# x-OSC_Gloves.net
KiCad netlist of a schematic drawn in EAGLE
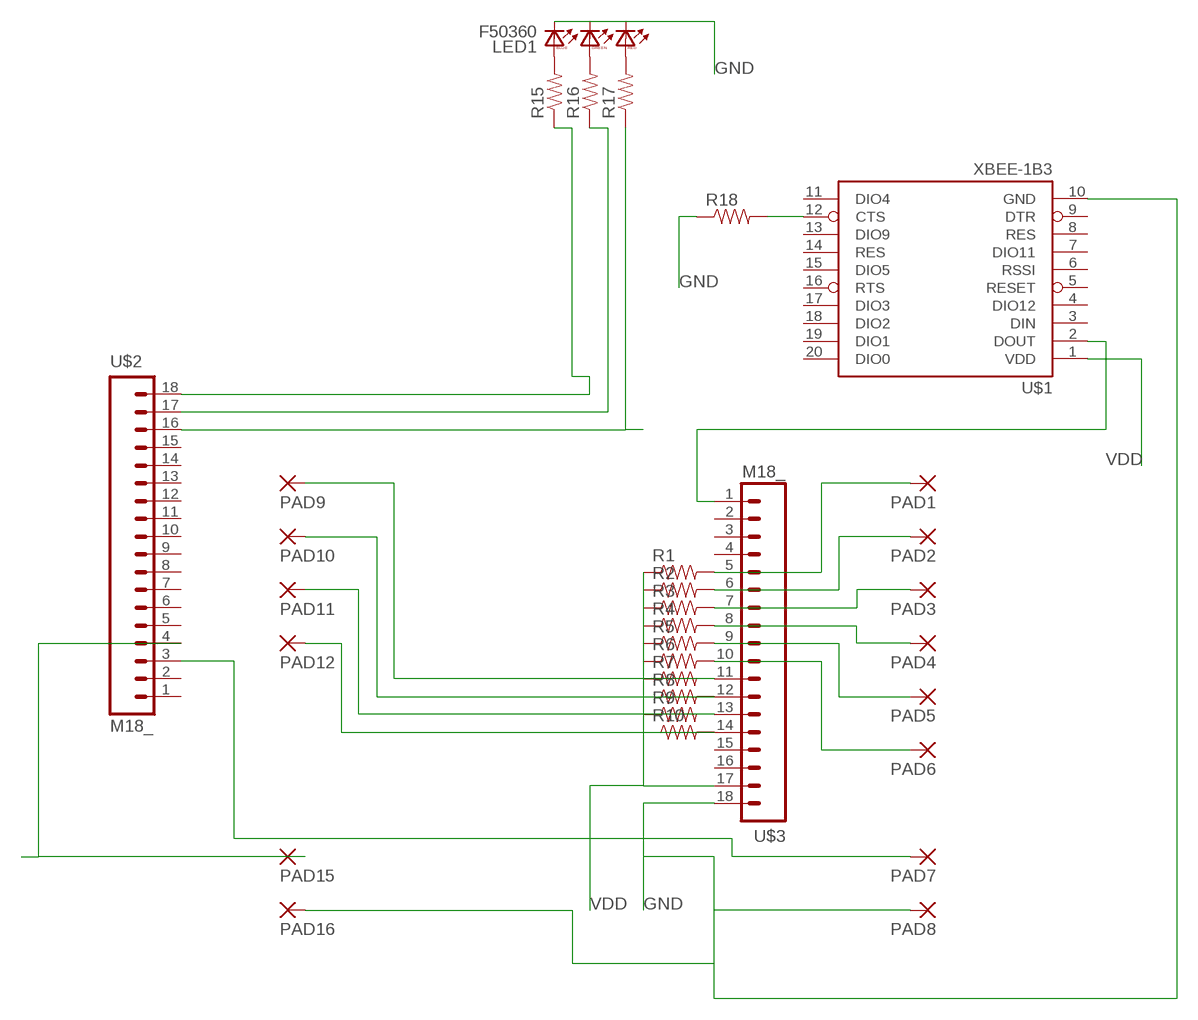
[diagram p0: schematic, sheet 1]

(export (version "E")
  (design (tool "Eeschema 10.0.6"))
  (components
    (comp (ref "LED1")
      (value "F50360")
      (footprint "eagle-import:F50360")
      (libsource (lib "eagle-import") (part "F50360"))
    )
    (comp (ref "PAD1")
      (value "3,81/1,4")
      (footprint "eagle-import:3,81_1,4")
      (libsource (lib "eagle-import") (part "3,81/1,4"))
    )
    (comp (ref "PAD2")
      (value "3,81/1,4")
      (footprint "eagle-import:3,81_1,4")
      (libsource (lib "eagle-import") (part "3,81/1,4"))
    )
    (comp (ref "PAD3")
      (value "3,81/1,4")
      (footprint "eagle-import:3,81_1,4")
      (libsource (lib "eagle-import") (part "3,81/1,4"))
    )
    (comp (ref "PAD4")
      (value "3,81/1,4")
      (footprint "eagle-import:3,81_1,4")
      (libsource (lib "eagle-import") (part "3,81/1,4"))
    )
    (comp (ref "PAD5")
      (value "3,81/1,4")
      (footprint "eagle-import:3,81_1,4")
      (libsource (lib "eagle-import") (part "3,81/1,4"))
    )
    (comp (ref "PAD6")
      (value "3,81/1,4")
      (footprint "eagle-import:3,81_1,4")
      (libsource (lib "eagle-import") (part "3,81/1,4"))
    )
    (comp (ref "PAD7")
      (value "3,81/1,4")
      (footprint "eagle-import:3,81_1,4")
      (libsource (lib "eagle-import") (part "3,81/1,4"))
    )
    (comp (ref "PAD8")
      (value "3,81/1,4")
      (footprint "eagle-import:3,81_1,4")
      (libsource (lib "eagle-import") (part "3,81/1,4"))
    )
    (comp (ref "PAD9")
      (value "3,81/1,4")
      (footprint "eagle-import:3,81_1,4")
      (libsource (lib "eagle-import") (part "3,81/1,4"))
    )
    (comp (ref "PAD10")
      (value "3,81/1,4")
      (footprint "eagle-import:3,81_1,4")
      (libsource (lib "eagle-import") (part "3,81/1,4"))
    )
    (comp (ref "PAD11")
      (value "3,81/1,4")
      (footprint "eagle-import:3,81_1,4")
      (libsource (lib "eagle-import") (part "3,81/1,4"))
    )
    (comp (ref "PAD12")
      (value "3,81/1,4")
      (footprint "eagle-import:3,81_1,4")
      (libsource (lib "eagle-import") (part "3,81/1,4"))
    )
    (comp (ref "PAD15")
      (value "3,81/1,4")
      (footprint "eagle-import:3,81_1,4")
      (libsource (lib "eagle-import") (part "3,81/1,4"))
    )
    (comp (ref "PAD16")
      (value "3,81/1,4")
      (footprint "eagle-import:3,81_1,4")
      (libsource (lib "eagle-import") (part "3,81/1,4"))
    )
    (comp (ref "R1")
      (value "RESISTOR0805-RES")
      (footprint "eagle-import:0805")
      (libsource (lib "eagle-import") (part "RESISTOR0805-RES"))
    )
    (comp (ref "R2")
      (value "RESISTOR0805-RES")
      (footprint "eagle-import:0805")
      (libsource (lib "eagle-import") (part "RESISTOR0805-RES"))
    )
    (comp (ref "R3")
      (value "RESISTOR0805-RES")
      (footprint "eagle-import:0805")
      (libsource (lib "eagle-import") (part "RESISTOR0805-RES"))
    )
    (comp (ref "R4")
      (value "RESISTOR0805-RES")
      (footprint "eagle-import:0805")
      (libsource (lib "eagle-import") (part "RESISTOR0805-RES"))
    )
    (comp (ref "R5")
      (value "RESISTOR0805-RES")
      (footprint "eagle-import:0805")
      (libsource (lib "eagle-import") (part "RESISTOR0805-RES"))
    )
    (comp (ref "R6")
      (value "RESISTOR0805-RES")
      (footprint "eagle-import:0805")
      (libsource (lib "eagle-import") (part "RESISTOR0805-RES"))
    )
    (comp (ref "R7")
      (value "RESISTOR0805-RES")
      (footprint "eagle-import:0805")
      (libsource (lib "eagle-import") (part "RESISTOR0805-RES"))
    )
    (comp (ref "R8")
      (value "RESISTOR0805-RES")
      (footprint "eagle-import:0805")
      (libsource (lib "eagle-import") (part "RESISTOR0805-RES"))
    )
    (comp (ref "R9")
      (value "RESISTOR0805-RES")
      (footprint "eagle-import:0805")
      (libsource (lib "eagle-import") (part "RESISTOR0805-RES"))
    )
    (comp (ref "R10")
      (value "RESISTOR0805-RES")
      (footprint "eagle-import:0805")
      (libsource (lib "eagle-import") (part "RESISTOR0805-RES"))
    )
    (comp (ref "R15")
      (value "RESISTOR0805-RES")
      (footprint "eagle-import:0805")
      (libsource (lib "eagle-import") (part "RESISTOR0805-RES"))
    )
    (comp (ref "R16")
      (value "RESISTOR0805-RES")
      (footprint "eagle-import:0805")
      (libsource (lib "eagle-import") (part "RESISTOR0805-RES"))
    )
    (comp (ref "R17")
      (value "RESISTOR0805-RES")
      (footprint "eagle-import:0805")
      (libsource (lib "eagle-import") (part "RESISTOR0805-RES"))
    )
    (comp (ref "R18")
      (value "RESISTOR0805-RES")
      (footprint "eagle-import:0805")
      (libsource (lib "eagle-import") (part "RESISTOR0805-RES"))
    )
    (comp (ref "U$1")
      (value "XBEE-1B3")
      (footprint "eagle-import:XBEE-SMD")
      (libsource (lib "eagle-import") (part "XBEE-1B3"))
    )
    (comp (ref "U$2")
      (value "M18_")
      (footprint "eagle-import:1X18")
      (libsource (lib "eagle-import") (part "M18_"))
    )
    (comp (ref "U$3")
      (value "M18_")
      (footprint "eagle-import:1X18")
      (libsource (lib "eagle-import") (part "M18_"))
    )
  )
  (nets
    (net (code "1") (name "/GND") (class "Default")
      (node (ref "LED1") (pin "BC") (pinfunction "BC_BC") (pintype "passive"))
      (node (ref "LED1") (pin "GC") (pinfunction "GC_GC") (pintype "passive"))
      (node (ref "LED1") (pin "RC") (pinfunction "RC_RC") (pintype "passive"))
      (node (ref "PAD16") (pin "1") (pinfunction "P_1") (pintype "passive"))
      (node (ref "PAD8") (pin "1") (pinfunction "P_1") (pintype "passive"))
      (node (ref "R18") (pin "1") (pinfunction "1_1") (pintype "passive"))
      (node (ref "U$1") (pin "10") (pinfunction "GND_10") (pintype "power_in"))
      (node (ref "U$3") (pin "18") (pinfunction "18_18") (pintype "passive"))
    )
    (net (code "2") (name "/VDD") (class "Default")
      (node (ref "R1") (pin "1") (pinfunction "1_1") (pintype "passive"))
      (node (ref "R10") (pin "1") (pinfunction "1_1") (pintype "passive"))
      (node (ref "R2") (pin "1") (pinfunction "1_1") (pintype "passive"))
      (node (ref "R3") (pin "1") (pinfunction "1_1") (pintype "passive"))
      (node (ref "R4") (pin "1") (pinfunction "1_1") (pintype "passive"))
      (node (ref "R5") (pin "1") (pinfunction "1_1") (pintype "passive"))
      (node (ref "R6") (pin "1") (pinfunction "1_1") (pintype "passive"))
      (node (ref "R7") (pin "1") (pinfunction "1_1") (pintype "passive"))
      (node (ref "R8") (pin "1") (pinfunction "1_1") (pintype "passive"))
      (node (ref "R9") (pin "1") (pinfunction "1_1") (pintype "passive"))
      (node (ref "U$1") (pin "1") (pinfunction "VDD_1") (pintype "power_in"))
      (node (ref "U$3") (pin "17") (pinfunction "17_17") (pintype "passive"))
    )
    (net (code "3") (name "Net-(LED1-PadBA)") (class "Default")
      (node (ref "LED1") (pin "BA") (pinfunction "BA_BA") (pintype "passive"))
      (node (ref "R15") (pin "2") (pinfunction "2_2") (pintype "passive"))
    )
    (net (code "4") (name "Net-(LED1-PadGA)") (class "Default")
      (node (ref "LED1") (pin "GA") (pinfunction "GA_GA") (pintype "passive"))
      (node (ref "R16") (pin "2") (pinfunction "2_2") (pintype "passive"))
    )
    (net (code "5") (name "Net-(LED1-PadRA)") (class "Default")
      (node (ref "LED1") (pin "RA") (pinfunction "RA_RA") (pintype "passive"))
      (node (ref "R17") (pin "2") (pinfunction "2_2") (pintype "passive"))
    )
    (net (code "6") (name "Net-(PAD1-P)") (class "Default")
      (node (ref "PAD1") (pin "1") (pinfunction "P_1") (pintype "passive"))
      (node (ref "R1") (pin "2") (pinfunction "2_2") (pintype "passive"))
      (node (ref "U$3") (pin "5") (pinfunction "5_5") (pintype "passive"))
    )
    (net (code "7") (name "Net-(PAD2-P)") (class "Default")
      (node (ref "PAD2") (pin "1") (pinfunction "P_1") (pintype "passive"))
      (node (ref "R2") (pin "2") (pinfunction "2_2") (pintype "passive"))
      (node (ref "U$3") (pin "6") (pinfunction "6_6") (pintype "passive"))
    )
    (net (code "8") (name "Net-(PAD3-P)") (class "Default")
      (node (ref "PAD3") (pin "1") (pinfunction "P_1") (pintype "passive"))
      (node (ref "R3") (pin "2") (pinfunction "2_2") (pintype "passive"))
      (node (ref "U$3") (pin "7") (pinfunction "7_7") (pintype "passive"))
    )
    (net (code "9") (name "Net-(PAD4-P)") (class "Default")
      (node (ref "PAD4") (pin "1") (pinfunction "P_1") (pintype "passive"))
      (node (ref "R4") (pin "2") (pinfunction "2_2") (pintype "passive"))
      (node (ref "U$3") (pin "8") (pinfunction "8_8") (pintype "passive"))
    )
    (net (code "10") (name "Net-(PAD5-P)") (class "Default")
      (node (ref "PAD5") (pin "1") (pinfunction "P_1") (pintype "passive"))
      (node (ref "R5") (pin "2") (pinfunction "2_2") (pintype "passive"))
      (node (ref "U$3") (pin "9") (pinfunction "9_9") (pintype "passive"))
    )
    (net (code "11") (name "Net-(PAD6-P)") (class "Default")
      (node (ref "PAD6") (pin "1") (pinfunction "P_1") (pintype "passive"))
      (node (ref "R6") (pin "2") (pinfunction "2_2") (pintype "passive"))
      (node (ref "U$3") (pin "10") (pinfunction "10_10") (pintype "passive"))
    )
    (net (code "12") (name "Net-(PAD7-P)") (class "Default")
      (node (ref "PAD7") (pin "1") (pinfunction "P_1") (pintype "passive"))
      (node (ref "U$2") (pin "3") (pinfunction "3_3") (pintype "passive"))
    )
    (net (code "13") (name "Net-(PAD9-P)") (class "Default")
      (node (ref "PAD9") (pin "1") (pinfunction "P_1") (pintype "passive"))
      (node (ref "R7") (pin "2") (pinfunction "2_2") (pintype "passive"))
      (node (ref "U$3") (pin "11") (pinfunction "11_11") (pintype "passive"))
    )
    (net (code "14") (name "Net-(PAD10-P)") (class "Default")
      (node (ref "PAD10") (pin "1") (pinfunction "P_1") (pintype "passive"))
      (node (ref "R8") (pin "2") (pinfunction "2_2") (pintype "passive"))
      (node (ref "U$3") (pin "12") (pinfunction "12_12") (pintype "passive"))
    )
    (net (code "15") (name "Net-(PAD11-P)") (class "Default")
      (node (ref "PAD11") (pin "1") (pinfunction "P_1") (pintype "passive"))
      (node (ref "R9") (pin "2") (pinfunction "2_2") (pintype "passive"))
      (node (ref "U$3") (pin "13") (pinfunction "13_13") (pintype "passive"))
    )
    (net (code "16") (name "Net-(PAD12-P)") (class "Default")
      (node (ref "PAD12") (pin "1") (pinfunction "P_1") (pintype "passive"))
      (node (ref "R10") (pin "2") (pinfunction "2_2") (pintype "passive"))
      (node (ref "U$3") (pin "14") (pinfunction "14_14") (pintype "passive"))
    )
    (net (code "17") (name "Net-(PAD15-P)") (class "Default")
      (node (ref "PAD15") (pin "1") (pinfunction "P_1") (pintype "passive"))
      (node (ref "U$2") (pin "4") (pinfunction "4_4") (pintype "passive"))
    )
    (net (code "18") (name "Net-(R15-Pad1)") (class "Default")
      (node (ref "R15") (pin "1") (pinfunction "1_1") (pintype "passive"))
      (node (ref "U$2") (pin "18") (pinfunction "18_18") (pintype "passive"))
    )
    (net (code "19") (name "Net-(R16-Pad1)") (class "Default")
      (node (ref "R16") (pin "1") (pinfunction "1_1") (pintype "passive"))
      (node (ref "U$2") (pin "17") (pinfunction "17_17") (pintype "passive"))
    )
    (net (code "20") (name "Net-(R17-Pad1)") (class "Default")
      (node (ref "R17") (pin "1") (pinfunction "1_1") (pintype "passive"))
      (node (ref "U$2") (pin "16") (pinfunction "16_16") (pintype "passive"))
    )
    (net (code "21") (name "Net-(U$1-CTS)") (class "Default")
      (node (ref "R18") (pin "2") (pinfunction "2_2") (pintype "passive"))
      (node (ref "U$1") (pin "12") (pinfunction "CTS_12") (pintype "output"))
    )
    (net (code "22") (name "Net-(U$1-DOUT)") (class "Default")
      (node (ref "U$1") (pin "2") (pinfunction "DOUT_2") (pintype "output"))
      (node (ref "U$3") (pin "1") (pinfunction "1_1") (pintype "passive"))
    )
    (net (code "23") (name "unconnected-(U$1-DIN-Pad3)") (class "Default")
      (node (ref "U$1") (pin "3") (pinfunction "DIN_3") (pintype "input"))
    )
    (net (code "24") (name "unconnected-(U$1-DIO0-Pad20)") (class "Default")
      (node (ref "U$1") (pin "20") (pinfunction "DIO0_20") (pintype "bidirectional"))
    )
    (net (code "25") (name "unconnected-(U$1-DIO1-Pad19)") (class "Default")
      (node (ref "U$1") (pin "19") (pinfunction "DIO1_19") (pintype "bidirectional"))
    )
    (net (code "26") (name "unconnected-(U$1-DIO2-Pad18)") (class "Default")
      (node (ref "U$1") (pin "18") (pinfunction "DIO2_18") (pintype "bidirectional"))
    )
    (net (code "27") (name "unconnected-(U$1-DIO3-Pad17)") (class "Default")
      (node (ref "U$1") (pin "17") (pinfunction "DIO3_17") (pintype "bidirectional"))
    )
    (net (code "28") (name "unconnected-(U$1-DIO4-Pad11)") (class "Default")
      (node (ref "U$1") (pin "11") (pinfunction "DIO4_11") (pintype "bidirectional"))
    )
    (net (code "29") (name "unconnected-(U$1-DIO5-Pad15)") (class "Default")
      (node (ref "U$1") (pin "15") (pinfunction "DIO5_15") (pintype "bidirectional"))
    )
    (net (code "30") (name "unconnected-(U$1-DIO9-Pad13)") (class "Default")
      (node (ref "U$1") (pin "13") (pinfunction "DIO9_13") (pintype "bidirectional"))
    )
    (net (code "31") (name "unconnected-(U$1-DIO11-Pad7)") (class "Default")
      (node (ref "U$1") (pin "7") (pinfunction "DIO11_7") (pintype "bidirectional"))
    )
    (net (code "32") (name "unconnected-(U$1-DIO12-Pad4)") (class "Default")
      (node (ref "U$1") (pin "4") (pinfunction "DIO12_4") (pintype "bidirectional"))
    )
    (net (code "33") (name "unconnected-(U$1-DTR-Pad9)") (class "Default")
      (node (ref "U$1") (pin "9") (pinfunction "DTR_9") (pintype "bidirectional"))
    )
    (net (code "34") (name "unconnected-(U$1-RES-Pad8)") (class "Default")
      (node (ref "U$1") (pin "8") (pinfunction "RES_8") (pintype "bidirectional"))
    )
    (net (code "35") (name "unconnected-(U$1-RES-Pad14)") (class "Default")
      (node (ref "U$1") (pin "14") (pinfunction "RES_14") (pintype "bidirectional"))
    )
    (net (code "36") (name "unconnected-(U$1-RESET-Pad5)") (class "Default")
      (node (ref "U$1") (pin "5") (pinfunction "RESET_5") (pintype "input"))
    )
    (net (code "37") (name "unconnected-(U$1-RSSI-Pad6)") (class "Default")
      (node (ref "U$1") (pin "6") (pinfunction "RSSI_6") (pintype "bidirectional"))
    )
    (net (code "38") (name "unconnected-(U$1-RTS-Pad16)") (class "Default")
      (node (ref "U$1") (pin "16") (pinfunction "RTS_16") (pintype "input"))
    )
    (net (code "39") (name "unconnected-(U$2-Pad1)") (class "Default")
      (node (ref "U$2") (pin "1") (pinfunction "1_1") (pintype "passive"))
    )
    (net (code "40") (name "unconnected-(U$2-Pad2)") (class "Default")
      (node (ref "U$2") (pin "2") (pinfunction "2_2") (pintype "passive"))
    )
    (net (code "41") (name "unconnected-(U$2-Pad5)") (class "Default")
      (node (ref "U$2") (pin "5") (pinfunction "5_5") (pintype "passive"))
    )
    (net (code "42") (name "unconnected-(U$2-Pad6)") (class "Default")
      (node (ref "U$2") (pin "6") (pinfunction "6_6") (pintype "passive"))
    )
    (net (code "43") (name "unconnected-(U$2-Pad7)") (class "Default")
      (node (ref "U$2") (pin "7") (pinfunction "7_7") (pintype "passive"))
    )
    (net (code "44") (name "unconnected-(U$2-Pad8)") (class "Default")
      (node (ref "U$2") (pin "8") (pinfunction "8_8") (pintype "passive"))
    )
    (net (code "45") (name "unconnected-(U$2-Pad9)") (class "Default")
      (node (ref "U$2") (pin "9") (pinfunction "9_9") (pintype "passive"))
    )
    (net (code "46") (name "unconnected-(U$2-Pad10)") (class "Default")
      (node (ref "U$2") (pin "10") (pinfunction "10_10") (pintype "passive"))
    )
    (net (code "47") (name "unconnected-(U$2-Pad11)") (class "Default")
      (node (ref "U$2") (pin "11") (pinfunction "11_11") (pintype "passive"))
    )
    (net (code "48") (name "unconnected-(U$2-Pad12)") (class "Default")
      (node (ref "U$2") (pin "12") (pinfunction "12_12") (pintype "passive"))
    )
    (net (code "49") (name "unconnected-(U$2-Pad13)") (class "Default")
      (node (ref "U$2") (pin "13") (pinfunction "13_13") (pintype "passive"))
    )
    (net (code "50") (name "unconnected-(U$2-Pad14)") (class "Default")
      (node (ref "U$2") (pin "14") (pinfunction "14_14") (pintype "passive"))
    )
    (net (code "51") (name "unconnected-(U$2-Pad15)") (class "Default")
      (node (ref "U$2") (pin "15") (pinfunction "15_15") (pintype "passive"))
    )
    (net (code "52") (name "unconnected-(U$3-Pad2)") (class "Default")
      (node (ref "U$3") (pin "2") (pinfunction "2_2") (pintype "passive"))
    )
    (net (code "53") (name "unconnected-(U$3-Pad3)") (class "Default")
      (node (ref "U$3") (pin "3") (pinfunction "3_3") (pintype "passive"))
    )
    (net (code "54") (name "unconnected-(U$3-Pad4)") (class "Default")
      (node (ref "U$3") (pin "4") (pinfunction "4_4") (pintype "passive"))
    )
    (net (code "55") (name "unconnected-(U$3-Pad15)") (class "Default")
      (node (ref "U$3") (pin "15") (pinfunction "15_15") (pintype "passive"))
    )
    (net (code "56") (name "unconnected-(U$3-Pad16)") (class "Default")
      (node (ref "U$3") (pin "16") (pinfunction "16_16") (pintype "passive"))
    )
  )
)
